# BlinkyBoard.net
KiCad netlist of a schematic drawn in EAGLE
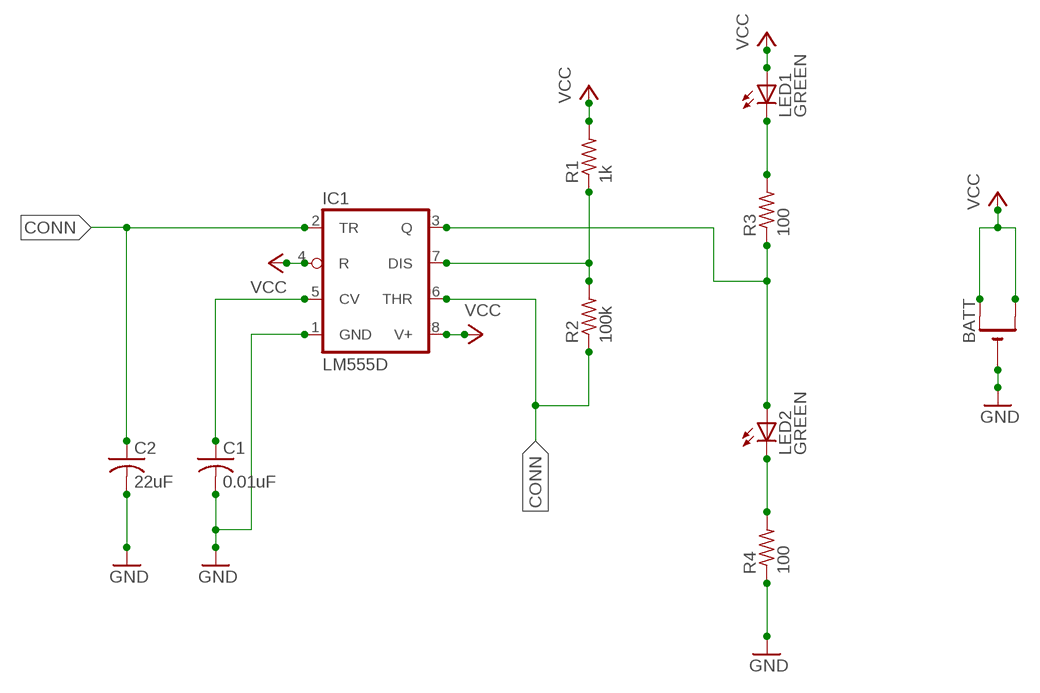
[diagram p0: schematic, sheet 1]

(export (version "E")
  (design (tool "Eeschema 10.0.6"))
  (components
    (comp (ref "BATT")
      (value "CR1220SMT")
      (footprint "eagle-import:CR1220-SMD")
      (libsource (lib "eagle-import") (part "CR1220SMT"))
    )
    (comp (ref "C1")
      (value "0.01uF")
      (footprint "eagle-import:C0805")
      (fields (field (name "MPN") "B32529C103K"))
      (libsource (lib "eagle-import") (part "C-USC0805"))
    )
    (comp (ref "C2")
      (value "22uF")
      (footprint "eagle-import:C0805")
      (fields (field (name "MPN") "NOJA226M006RWJ"))
      (libsource (lib "eagle-import") (part "C-USC0805"))
    )
    (comp (ref "IC1")
      (value "LM555D")
      (footprint "eagle-import:SO08")
      (libsource (lib "eagle-import") (part "555DLM"))
    )
    (comp (ref "LED1")
      (value "GREEN")
      (footprint "eagle-import:CHIP-LED0805")
      (libsource (lib "eagle-import") (part "LEDCHIP-LED0805"))
    )
    (comp (ref "LED2")
      (value "GREEN")
      (footprint "eagle-import:CHIP-LED0805")
      (libsource (lib "eagle-import") (part "LEDCHIP-LED0805"))
    )
    (comp (ref "R1")
      (value "1k")
      (footprint "eagle-import:R0805")
      (libsource (lib "eagle-import") (part "R-US_R0805"))
    )
    (comp (ref "R2")
      (value "100k")
      (footprint "eagle-import:R0805")
      (libsource (lib "eagle-import") (part "R-US_R0805"))
    )
    (comp (ref "R3")
      (value "100")
      (footprint "eagle-import:R0805")
      (libsource (lib "eagle-import") (part "R-US_R0805"))
    )
    (comp (ref "R4")
      (value "100")
      (footprint "eagle-import:R0805")
      (libsource (lib "eagle-import") (part "R-US_R0805"))
    )
  )
  (nets
    (net (code "1") (name "CONN") (class "Default")
      (node (ref "C2") (pin "1") (pinfunction "1_1") (pintype "passive"))
      (node (ref "IC1") (pin "2") (pinfunction "TR_2") (pintype "input"))
      (node (ref "IC1") (pin "6") (pinfunction "THR_6") (pintype "input"))
      (node (ref "R2") (pin "1") (pinfunction "1_1") (pintype "passive"))
    )
    (net (code "2") (name "GND") (class "Default")
      (node (ref "BATT") (pin "-") (pinfunction "-_-") (pintype "passive"))
      (node (ref "C1") (pin "2") (pinfunction "2_2") (pintype "passive"))
      (node (ref "C2") (pin "2") (pinfunction "2_2") (pintype "passive"))
      (node (ref "IC1") (pin "1") (pinfunction "GND_1") (pintype "power_in"))
      (node (ref "R4") (pin "1") (pinfunction "1_1") (pintype "passive"))
    )
    (net (code "3") (name "Net-(IC1-CV)") (class "Default")
      (node (ref "C1") (pin "1") (pinfunction "1_1") (pintype "passive"))
      (node (ref "IC1") (pin "5") (pinfunction "CV_5") (pintype "input"))
    )
    (net (code "4") (name "Net-(IC1-DIS)") (class "Default")
      (node (ref "IC1") (pin "7") (pinfunction "DIS_7") (pintype "input"))
      (node (ref "R1") (pin "1") (pinfunction "1_1") (pintype "passive"))
      (node (ref "R2") (pin "2") (pinfunction "2_2") (pintype "passive"))
    )
    (net (code "5") (name "Net-(IC1-Q)") (class "Default")
      (node (ref "IC1") (pin "3") (pinfunction "Q_3") (pintype "output"))
      (node (ref "LED2") (pin "A") (pinfunction "A_A") (pintype "passive"))
      (node (ref "R3") (pin "1") (pinfunction "1_1") (pintype "passive"))
    )
    (net (code "6") (name "Net-(LED1-PadC)") (class "Default")
      (node (ref "LED1") (pin "C") (pinfunction "C_C") (pintype "passive"))
      (node (ref "R3") (pin "2") (pinfunction "2_2") (pintype "passive"))
    )
    (net (code "7") (name "Net-(LED2-PadC)") (class "Default")
      (node (ref "LED2") (pin "C") (pinfunction "C_C") (pintype "passive"))
      (node (ref "R4") (pin "2") (pinfunction "2_2") (pintype "passive"))
    )
    (net (code "8") (name "VCC") (class "Default")
      (node (ref "BATT") (pin "+$1") (pinfunction "+_+$1") (pintype "passive"))
      (node (ref "BATT") (pin "+$2") (pinfunction "+1_+$2") (pintype "passive"))
      (node (ref "IC1") (pin "4") (pinfunction "R_4") (pintype "input"))
      (node (ref "IC1") (pin "8") (pinfunction "V+_8") (pintype "power_in"))
      (node (ref "LED1") (pin "A") (pinfunction "A_A") (pintype "passive"))
      (node (ref "R1") (pin "2") (pinfunction "2_2") (pintype "passive"))
    )
  )
)
